# Power_Supply_adi.net
KiCad netlist of a schematic drawn in EAGLE
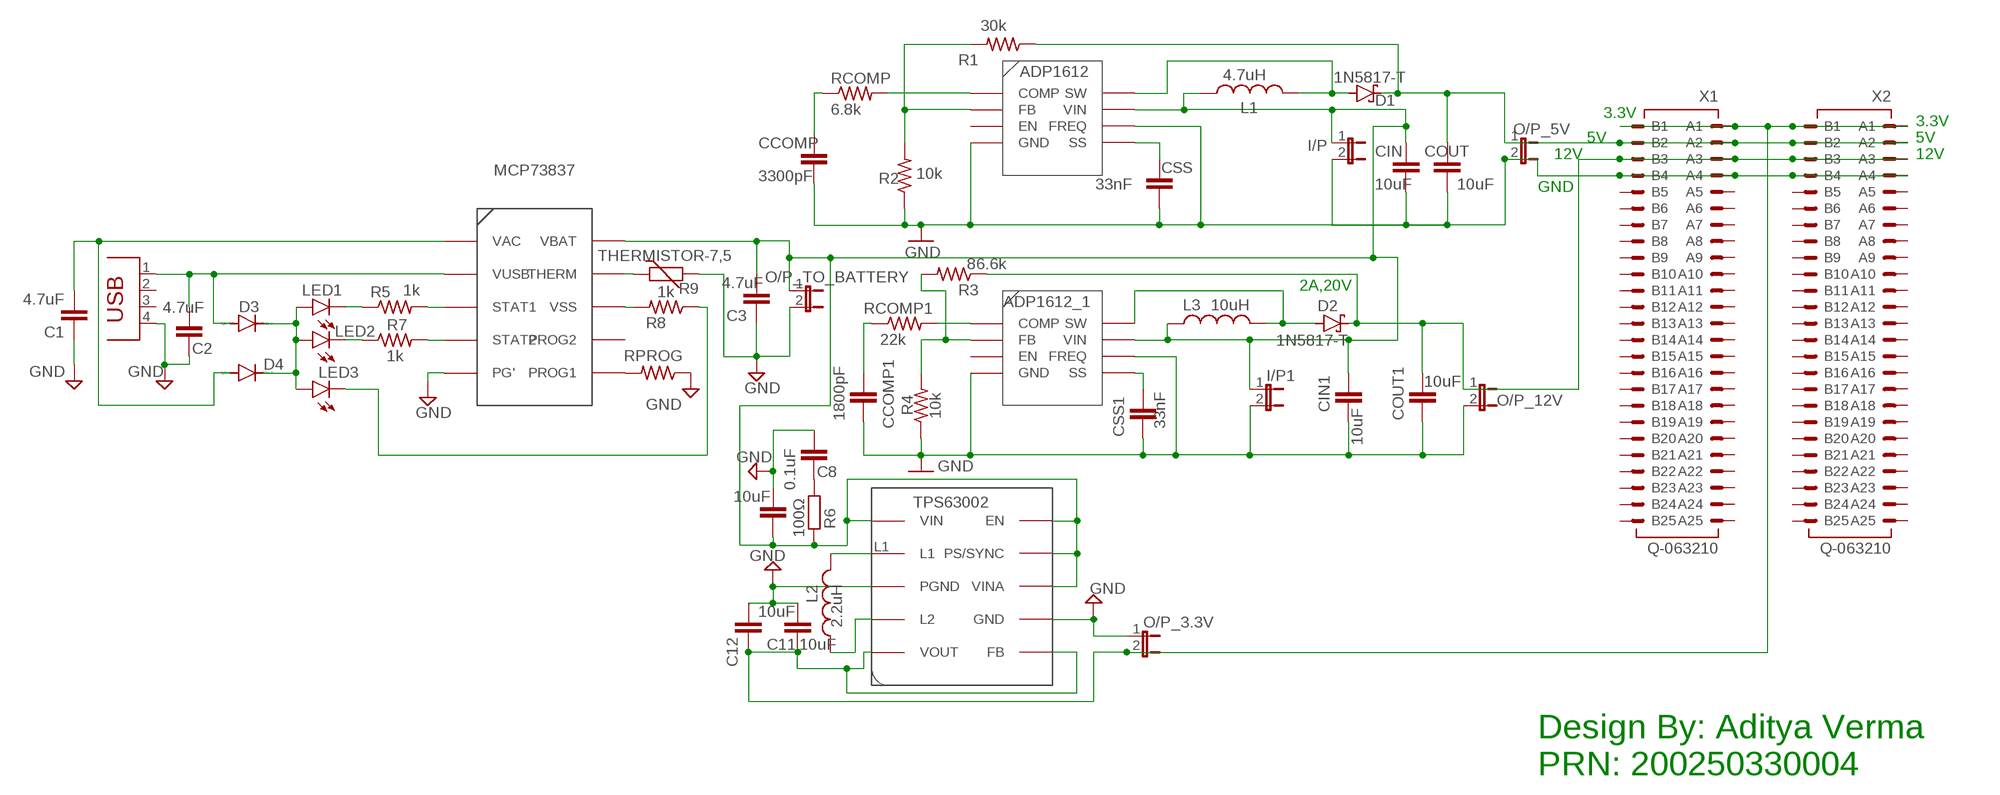
[diagram p0: schematic, sheet 1]

(export (version "E")
  (design (tool "Eeschema 10.0.6"))
  (components
    (comp (ref "ADP1612")
      (value "ADP1612_DEV")
      (footprint "eagle-import:ADP1612_FOOT")
      (libsource (lib "eagle-import") (part "ADP1612_DEV"))
    )
    (comp (ref "ADP1612_1")
      (value "ADP1612_DEV")
      (footprint "eagle-import:ADP1612_FOOT")
      (libsource (lib "eagle-import") (part "ADP1612_DEV"))
    )
    (comp (ref "C1")
      (value "4.7uF")
      (footprint "eagle-import:C2.5-3")
      (libsource (lib "eagle-import") (part "C2,5-3"))
    )
    (comp (ref "C2")
      (value "4.7uF")
      (footprint "eagle-import:C2.5-3")
      (libsource (lib "eagle-import") (part "C2,5-3"))
    )
    (comp (ref "C3")
      (value "4.7uF")
      (footprint "eagle-import:C2.5-3")
      (libsource (lib "eagle-import") (part "C2,5-3"))
    )
    (comp (ref "C8")
      (value "0.1uF")
      (footprint "eagle-import:C2.5-2")
      (libsource (lib "eagle-import") (part "C2.5/2"))
    )
    (comp (ref "C10")
      (value "10uF")
      (footprint "eagle-import:C2.5-2")
      (libsource (lib "eagle-import") (part "C2.5/2"))
    )
    (comp (ref "C11")
      (value "10uF")
      (footprint "eagle-import:C2.5-2")
      (libsource (lib "eagle-import") (part "C2.5/2"))
    )
    (comp (ref "C12")
      (value "10uF")
      (footprint "eagle-import:C2.5-2")
      (libsource (lib "eagle-import") (part "C2.5/2"))
    )
    (comp (ref "CCOMP")
      (value "3300pF")
      (footprint "eagle-import:C2.5-3")
      (libsource (lib "eagle-import") (part "C2,5-3"))
    )
    (comp (ref "CCOMP1")
      (value "1800pF")
      (footprint "eagle-import:C2.5-3")
      (libsource (lib "eagle-import") (part "C2,5-3"))
    )
    (comp (ref "CIN")
      (value "10uF")
      (footprint "eagle-import:C2.5-3")
      (libsource (lib "eagle-import") (part "C2,5-3"))
    )
    (comp (ref "CIN1")
      (value "10uF")
      (footprint "eagle-import:C2.5-3")
      (libsource (lib "eagle-import") (part "C2,5-3"))
    )
    (comp (ref "COUT")
      (value "10uF")
      (footprint "eagle-import:C2.5-3")
      (libsource (lib "eagle-import") (part "C2,5-3"))
    )
    (comp (ref "COUT1")
      (value "10uF")
      (footprint "eagle-import:C2.5-3")
      (libsource (lib "eagle-import") (part "C2,5-3"))
    )
    (comp (ref "CSS")
      (value "33nF")
      (footprint "eagle-import:C2.5-3")
      (libsource (lib "eagle-import") (part "C2,5-3"))
    )
    (comp (ref "CSS1")
      (value "33nF")
      (footprint "eagle-import:C2.5-3")
      (libsource (lib "eagle-import") (part "C2,5-3"))
    )
    (comp (ref "D1")
      (value "1N5817-T")
      (footprint "eagle-import:DO41-7.6")
      (libsource (lib "eagle-import") (part "1N5817-T"))
    )
    (comp (ref "D2")
      (value "1N5817-T")
      (footprint "eagle-import:DO41-7.6")
      (libsource (lib "eagle-import") (part "1N5817-T"))
    )
    (comp (ref "D3")
      (value "1N4004")
      (footprint "eagle-import:DO41-10")
      (libsource (lib "eagle-import") (part "1N4004"))
    )
    (comp (ref "D4")
      (value "1N4004")
      (footprint "eagle-import:DO41-10")
      (libsource (lib "eagle-import") (part "1N4004"))
    )
    (comp (ref "I/P")
      (value "JP1E")
      (footprint "eagle-import:JP1")
      (libsource (lib "eagle-import") (part "JP1E"))
    )
    (comp (ref "I/P1")
      (value "JP1E")
      (footprint "eagle-import:JP1")
      (libsource (lib "eagle-import") (part "JP1E"))
    )
    (comp (ref "L1")
      (value "4.7uH")
      (footprint "eagle-import:0204_7")
      (libsource (lib "eagle-import") (part "L-US0204/7"))
    )
    (comp (ref "L2")
      (value "2.2uH")
      (footprint "eagle-import:0207_7")
      (libsource (lib "eagle-import") (part "L-US0207/7"))
    )
    (comp (ref "L3")
      (value "10uH")
      (footprint "eagle-import:0204_7")
      (libsource (lib "eagle-import") (part "L-US0204/7"))
    )
    (comp (ref "LED1")
      (value "LED3MM")
      (footprint "eagle-import:LED3MM")
      (libsource (lib "eagle-import") (part "LED3MM"))
    )
    (comp (ref "LED2")
      (value "LEDLD260")
      (footprint "eagle-import:LD260")
      (libsource (lib "eagle-import") (part "LEDLD260"))
    )
    (comp (ref "LED3")
      (value "LED3MM")
      (footprint "eagle-import:LED3MM")
      (libsource (lib "eagle-import") (part "LED3MM"))
    )
    (comp (ref "MCP73837")
      (value "MCP73837-DEV")
      (footprint "eagle-import:MCP73837")
      (libsource (lib "eagle-import") (part "MCP73837-DEV"))
    )
    (comp (ref "O/P_3.3V")
      (value "JP1E")
      (footprint "eagle-import:JP1")
      (libsource (lib "eagle-import") (part "JP1E"))
    )
    (comp (ref "O/P_5V")
      (value "JP1E")
      (footprint "eagle-import:JP1")
      (libsource (lib "eagle-import") (part "JP1E"))
    )
    (comp (ref "O/P_12V")
      (value "JP1E")
      (footprint "eagle-import:JP1")
      (libsource (lib "eagle-import") (part "JP1E"))
    )
    (comp (ref "O/P_TO_BATTERY")
      (value "JP1E")
      (footprint "eagle-import:JP1")
      (libsource (lib "eagle-import") (part "JP1E"))
    )
    (comp (ref "R1")
      (value "30k")
      (footprint "eagle-import:0204V")
      (libsource (lib "eagle-import") (part "R-US_0204/2V"))
    )
    (comp (ref "R2")
      (value "10k")
      (footprint "eagle-import:0204V")
      (libsource (lib "eagle-import") (part "R-US_0204/2V"))
    )
    (comp (ref "R3")
      (value "86.6k")
      (footprint "eagle-import:0204V")
      (libsource (lib "eagle-import") (part "R-US_0204/2V"))
    )
    (comp (ref "R4")
      (value "10k")
      (footprint "eagle-import:0204V")
      (libsource (lib "eagle-import") (part "R-US_0204/2V"))
    )
    (comp (ref "R5")
      (value "1k")
      (footprint "eagle-import:0204V")
      (libsource (lib "eagle-import") (part "R-US_0204/2V"))
    )
    (comp (ref "R6")
      (value "100Ω")
      (footprint "eagle-import:0207_10")
      (libsource (lib "eagle-import") (part "R-EU_0207/10"))
    )
    (comp (ref "R7")
      (value "1k")
      (footprint "eagle-import:0204V")
      (libsource (lib "eagle-import") (part "R-US_0204/2V"))
    )
    (comp (ref "R8")
      (value "1k")
      (footprint "eagle-import:0204V")
      (libsource (lib "eagle-import") (part "R-US_0204/2V"))
    )
    (comp (ref "R9")
      (value "THERMISTOR-7,5")
      (footprint "eagle-import:R-7,5")
      (libsource (lib "eagle-import") (part "THERMISTOR-7,5"))
    )
    (comp (ref "RCOMP")
      (value "6.8k")
      (footprint "eagle-import:0204V")
      (libsource (lib "eagle-import") (part "R-US_0204/2V"))
    )
    (comp (ref "RCOMP1")
      (value "22k")
      (footprint "eagle-import:0204V")
      (libsource (lib "eagle-import") (part "R-US_0204/2V"))
    )
    (comp (ref "RPROG")
      (value "R-US_0204/2V")
      (footprint "eagle-import:0204V")
      (libsource (lib "eagle-import") (part "R-US_0204/2V"))
    )
    (comp (ref "TPS63002")
      (value "TPS63002")
      (footprint "eagle-import:TPS63002")
      (libsource (lib "eagle-import") (part "TPS63002"))
    )
    (comp (ref "USB")
      (value "PN61729")
      (footprint "eagle-import:PN61729")
      (libsource (lib "eagle-import") (part "PN61729"))
    )
    (comp (ref "X1")
      (value "Q-063210")
      (footprint "eagle-import:063210")
      (libsource (lib "eagle-import") (part "Q-063210"))
    )
    (comp (ref "X2")
      (value "Q-063210")
      (footprint "eagle-import:063210")
      (libsource (lib "eagle-import") (part "Q-063210"))
    )
  )
  (nets
    (net (code "1") (name "GND") (class "Default")
      (node (ref "ADP1612") (pin "FREQ") (pinfunction "FREQ_FREQ") (pintype "bidirectional"))
      (node (ref "ADP1612") (pin "GND") (pinfunction "GND_GND") (pintype "bidirectional"))
      (node (ref "ADP1612_1") (pin "FREQ") (pinfunction "FREQ_FREQ") (pintype "bidirectional"))
      (node (ref "ADP1612_1") (pin "GND") (pinfunction "GND_GND") (pintype "bidirectional"))
      (node (ref "C1") (pin "1") (pinfunction "1_1") (pintype "passive"))
      (node (ref "C10") (pin "2") (pinfunction "2_2") (pintype "passive"))
      (node (ref "C11") (pin "2") (pinfunction "2_2") (pintype "passive"))
      (node (ref "C12") (pin "2") (pinfunction "2_2") (pintype "passive"))
      (node (ref "C2") (pin "1") (pinfunction "1_1") (pintype "passive"))
      (node (ref "C3") (pin "1") (pinfunction "1_1") (pintype "passive"))
      (node (ref "C8") (pin "2") (pinfunction "2_2") (pintype "passive"))
      (node (ref "CCOMP") (pin "2") (pinfunction "2_2") (pintype "passive"))
      (node (ref "CCOMP1") (pin "2") (pinfunction "2_2") (pintype "passive"))
      (node (ref "CIN") (pin "2") (pinfunction "2_2") (pintype "passive"))
      (node (ref "CIN1") (pin "2") (pinfunction "2_2") (pintype "passive"))
      (node (ref "COUT") (pin "2") (pinfunction "2_2") (pintype "passive"))
      (node (ref "COUT1") (pin "2") (pinfunction "2_2") (pintype "passive"))
      (node (ref "CSS") (pin "2") (pinfunction "2_2") (pintype "passive"))
      (node (ref "CSS1") (pin "2") (pinfunction "2_2") (pintype "passive"))
      (node (ref "I/P") (pin "2") (pinfunction "2_2") (pintype "passive"))
      (node (ref "I/P1") (pin "2") (pinfunction "2_2") (pintype "passive"))
      (node (ref "MCP73837") (pin "PG'") (pinfunction "PG'_PG'") (pintype "bidirectional"))
      (node (ref "O/P_12V") (pin "2") (pinfunction "2_2") (pintype "passive"))
      (node (ref "O/P_3.3V") (pin "1") (pinfunction "1_1") (pintype "passive"))
      (node (ref "O/P_5V") (pin "2") (pinfunction "2_2") (pintype "passive"))
      (node (ref "O/P_TO_BATTERY") (pin "2") (pinfunction "2_2") (pintype "passive"))
      (node (ref "R2") (pin "1") (pinfunction "1_1") (pintype "passive"))
      (node (ref "R4") (pin "1") (pinfunction "1_1") (pintype "passive"))
      (node (ref "R9") (pin "2") (pinfunction "2_2") (pintype "passive"))
      (node (ref "RPROG") (pin "1") (pinfunction "1_1") (pintype "passive"))
      (node (ref "TPS63002") (pin "GND") (pinfunction "GND_GND") (pintype "bidirectional"))
      (node (ref "TPS63002") (pin "PGND") (pinfunction "PGND_PGND") (pintype "bidirectional"))
      (node (ref "USB") (pin "4") (pinfunction "4_4") (pintype "passive"))
      (node (ref "X1") (pin "A4") (pinfunction "A4_A4") (pintype "passive"))
      (node (ref "X1") (pin "B4") (pinfunction "B4_B4") (pintype "passive"))
      (node (ref "X2") (pin "A4") (pinfunction "A4_A4") (pintype "passive"))
      (node (ref "X2") (pin "B4") (pinfunction "B4_B4") (pintype "passive"))
    )
    (net (code "2") (name "Net-(ADP1612-PadCOMP)") (class "Default")
      (node (ref "ADP1612") (pin "COMP") (pinfunction "COMP_COMP") (pintype "bidirectional"))
      (node (ref "RCOMP") (pin "2") (pinfunction "2_2") (pintype "passive"))
    )
    (net (code "3") (name "Net-(ADP1612-PadFB)") (class "Default")
      (node (ref "ADP1612") (pin "FB") (pinfunction "FB_FB") (pintype "bidirectional"))
      (node (ref "R1") (pin "2") (pinfunction "2_2") (pintype "passive"))
      (node (ref "R2") (pin "2") (pinfunction "2_2") (pintype "passive"))
    )
    (net (code "4") (name "Net-(ADP1612-PadSS)") (class "Default")
      (node (ref "ADP1612") (pin "SS") (pinfunction "SS_SS") (pintype "bidirectional"))
      (node (ref "CSS") (pin "1") (pinfunction "1_1") (pintype "passive"))
    )
    (net (code "5") (name "Net-(ADP1612-PadSW)") (class "Default")
      (node (ref "ADP1612") (pin "SW") (pinfunction "SW_SW") (pintype "bidirectional"))
      (node (ref "D1") (pin "A") (pinfunction "A_A") (pintype "passive"))
      (node (ref "L1") (pin "2") (pinfunction "2_2") (pintype "passive"))
    )
    (net (code "6") (name "Net-(ADP1612-PadVIN)") (class "Default")
      (node (ref "ADP1612") (pin "VIN") (pinfunction "VIN_VIN") (pintype "bidirectional"))
      (node (ref "ADP1612_1") (pin "VIN") (pinfunction "VIN_VIN") (pintype "bidirectional"))
      (node (ref "C10") (pin "1") (pinfunction "1_1") (pintype "passive"))
      (node (ref "C3") (pin "2") (pinfunction "2_2") (pintype "passive"))
      (node (ref "CIN") (pin "1") (pinfunction "1_1") (pintype "passive"))
      (node (ref "CIN1") (pin "1") (pinfunction "1_1") (pintype "passive"))
      (node (ref "I/P") (pin "1") (pinfunction "1_1") (pintype "passive"))
      (node (ref "I/P1") (pin "1") (pinfunction "1_1") (pintype "passive"))
      (node (ref "L1") (pin "1") (pinfunction "1_1") (pintype "passive"))
      (node (ref "L3") (pin "1") (pinfunction "1_1") (pintype "passive"))
      (node (ref "MCP73837") (pin "VBAT") (pinfunction "VBAT_VBAT") (pintype "bidirectional"))
      (node (ref "O/P_TO_BATTERY") (pin "1") (pinfunction "1_1") (pintype "passive"))
      (node (ref "R6") (pin "1") (pinfunction "1_1") (pintype "passive"))
      (node (ref "TPS63002") (pin "EN") (pinfunction "EN_EN") (pintype "bidirectional"))
      (node (ref "TPS63002") (pin "PS/SYNC") (pinfunction "PS/SYNC_PS/SYNC") (pintype "bidirectional"))
      (node (ref "TPS63002") (pin "VIN") (pinfunction "VIN_VIN") (pintype "bidirectional"))
      (node (ref "TPS63002") (pin "VINA") (pinfunction "VINA_VINA") (pintype "bidirectional"))
    )
    (net (code "7") (name "Net-(ADP1612_1-PadCOMP)") (class "Default")
      (node (ref "ADP1612_1") (pin "COMP") (pinfunction "COMP_COMP") (pintype "bidirectional"))
      (node (ref "RCOMP1") (pin "2") (pinfunction "2_2") (pintype "passive"))
    )
    (net (code "8") (name "Net-(ADP1612_1-PadFB)") (class "Default")
      (node (ref "ADP1612_1") (pin "FB") (pinfunction "FB_FB") (pintype "bidirectional"))
      (node (ref "R3") (pin "2") (pinfunction "2_2") (pintype "passive"))
      (node (ref "R4") (pin "2") (pinfunction "2_2") (pintype "passive"))
    )
    (net (code "9") (name "Net-(ADP1612_1-PadSS)") (class "Default")
      (node (ref "ADP1612_1") (pin "SS") (pinfunction "SS_SS") (pintype "bidirectional"))
      (node (ref "CSS1") (pin "1") (pinfunction "1_1") (pintype "passive"))
    )
    (net (code "10") (name "Net-(ADP1612_1-PadSW)") (class "Default")
      (node (ref "ADP1612_1") (pin "SW") (pinfunction "SW_SW") (pintype "bidirectional"))
      (node (ref "D2") (pin "A") (pinfunction "A_A") (pintype "passive"))
      (node (ref "L3") (pin "2") (pinfunction "2_2") (pintype "passive"))
    )
    (net (code "11") (name "Net-(C1-Pad2)") (class "Default")
      (node (ref "C1") (pin "2") (pinfunction "2_2") (pintype "passive"))
      (node (ref "D4") (pin "A") (pinfunction "A_A") (pintype "passive"))
      (node (ref "MCP73837") (pin "VAC") (pinfunction "VAC_VAC") (pintype "bidirectional"))
    )
    (net (code "12") (name "Net-(C2-Pad2)") (class "Default")
      (node (ref "C2") (pin "2") (pinfunction "2_2") (pintype "passive"))
      (node (ref "D3") (pin "A") (pinfunction "A_A") (pintype "passive"))
      (node (ref "MCP73837") (pin "VUSB") (pinfunction "VUSB_VUSB") (pintype "bidirectional"))
      (node (ref "USB") (pin "1") (pinfunction "1_1") (pintype "passive"))
    )
    (net (code "13") (name "Net-(C8-Pad1)") (class "Default")
      (node (ref "C8") (pin "1") (pinfunction "1_1") (pintype "passive"))
      (node (ref "R6") (pin "2") (pinfunction "2_2") (pintype "passive"))
    )
    (net (code "14") (name "Net-(C11-Pad1)") (class "Default")
      (node (ref "C11") (pin "1") (pinfunction "1_1") (pintype "passive"))
      (node (ref "C12") (pin "1") (pinfunction "1_1") (pintype "passive"))
      (node (ref "O/P_3.3V") (pin "2") (pinfunction "2_2") (pintype "passive"))
      (node (ref "TPS63002") (pin "FB") (pinfunction "FB_FB") (pintype "bidirectional"))
      (node (ref "TPS63002") (pin "VOUT") (pinfunction "VOUT_VOUT") (pintype "bidirectional"))
      (node (ref "X1") (pin "A1") (pinfunction "A1_A1") (pintype "passive"))
      (node (ref "X1") (pin "B1") (pinfunction "B1_B1") (pintype "passive"))
      (node (ref "X2") (pin "A1") (pinfunction "A1_A1") (pintype "passive"))
      (node (ref "X2") (pin "B1") (pinfunction "B1_B1") (pintype "passive"))
    )
    (net (code "15") (name "Net-(CCOMP-Pad1)") (class "Default")
      (node (ref "CCOMP") (pin "1") (pinfunction "1_1") (pintype "passive"))
      (node (ref "RCOMP") (pin "1") (pinfunction "1_1") (pintype "passive"))
    )
    (net (code "16") (name "Net-(CCOMP1-Pad1)") (class "Default")
      (node (ref "CCOMP1") (pin "1") (pinfunction "1_1") (pintype "passive"))
      (node (ref "RCOMP1") (pin "1") (pinfunction "1_1") (pintype "passive"))
    )
    (net (code "17") (name "Net-(COUT-Pad1)") (class "Default")
      (node (ref "COUT") (pin "1") (pinfunction "1_1") (pintype "passive"))
      (node (ref "D1") (pin "C") (pinfunction "C_C") (pintype "passive"))
      (node (ref "O/P_5V") (pin "1") (pinfunction "1_1") (pintype "passive"))
      (node (ref "R1") (pin "1") (pinfunction "1_1") (pintype "passive"))
      (node (ref "X1") (pin "A2") (pinfunction "A2_A2") (pintype "passive"))
      (node (ref "X1") (pin "B2") (pinfunction "B2_B2") (pintype "passive"))
      (node (ref "X2") (pin "A2") (pinfunction "A2_A2") (pintype "passive"))
      (node (ref "X2") (pin "B2") (pinfunction "B2_B2") (pintype "passive"))
    )
    (net (code "18") (name "Net-(COUT1-Pad1)") (class "Default")
      (node (ref "COUT1") (pin "1") (pinfunction "1_1") (pintype "passive"))
      (node (ref "D2") (pin "C") (pinfunction "C_C") (pintype "passive"))
      (node (ref "O/P_12V") (pin "1") (pinfunction "1_1") (pintype "passive"))
      (node (ref "R3") (pin "1") (pinfunction "1_1") (pintype "passive"))
      (node (ref "X1") (pin "A3") (pinfunction "A3_A3") (pintype "passive"))
      (node (ref "X1") (pin "B3") (pinfunction "B3_B3") (pintype "passive"))
      (node (ref "X2") (pin "A3") (pinfunction "A3_A3") (pintype "passive"))
      (node (ref "X2") (pin "B3") (pinfunction "B3_B3") (pintype "passive"))
    )
    (net (code "19") (name "Net-(D3-PadC)") (class "Default")
      (node (ref "D3") (pin "C") (pinfunction "C_C") (pintype "passive"))
      (node (ref "D4") (pin "C") (pinfunction "C_C") (pintype "passive"))
      (node (ref "LED1") (pin "A") (pinfunction "A_A") (pintype "passive"))
      (node (ref "LED2") (pin "A") (pinfunction "A_A") (pintype "passive"))
      (node (ref "LED3") (pin "A") (pinfunction "A_A") (pintype "passive"))
    )
    (net (code "20") (name "Net-(L2-Pad1)") (class "Default")
      (node (ref "L2") (pin "1") (pinfunction "1_1") (pintype "passive"))
      (node (ref "TPS63002") (pin "L1") (pinfunction "L1_L1") (pintype "bidirectional"))
    )
    (net (code "21") (name "Net-(L2-Pad2)") (class "Default")
      (node (ref "L2") (pin "2") (pinfunction "2_2") (pintype "passive"))
      (node (ref "TPS63002") (pin "L2") (pinfunction "L2_L2") (pintype "bidirectional"))
    )
    (net (code "22") (name "Net-(LED1-C)") (class "Default")
      (node (ref "LED1") (pin "K") (pinfunction "C_K") (pintype "passive"))
      (node (ref "R5") (pin "1") (pinfunction "1_1") (pintype "passive"))
    )
    (net (code "23") (name "Net-(LED2-C)") (class "Default")
      (node (ref "LED2") (pin "K") (pinfunction "C_K") (pintype "passive"))
      (node (ref "R7") (pin "1") (pinfunction "1_1") (pintype "passive"))
    )
    (net (code "24") (name "Net-(LED3-C)") (class "Default")
      (node (ref "LED3") (pin "K") (pinfunction "C_K") (pintype "passive"))
      (node (ref "R8") (pin "1") (pinfunction "1_1") (pintype "passive"))
    )
    (net (code "25") (name "Net-(MCP73837-PadPROG1)") (class "Default")
      (node (ref "MCP73837") (pin "PROG1") (pinfunction "PROG1_PROG1") (pintype "bidirectional"))
      (node (ref "RPROG") (pin "2") (pinfunction "2_2") (pintype "passive"))
    )
    (net (code "26") (name "Net-(MCP73837-PadSTAT1)") (class "Default")
      (node (ref "MCP73837") (pin "STAT1") (pinfunction "STAT1_STAT1") (pintype "bidirectional"))
      (node (ref "R5") (pin "2") (pinfunction "2_2") (pintype "passive"))
    )
    (net (code "27") (name "Net-(MCP73837-PadSTAT2)") (class "Default")
      (node (ref "MCP73837") (pin "STAT2") (pinfunction "STAT2_STAT2") (pintype "bidirectional"))
      (node (ref "R7") (pin "2") (pinfunction "2_2") (pintype "passive"))
    )
    (net (code "28") (name "Net-(MCP73837-PadTHERM)") (class "Default")
      (node (ref "MCP73837") (pin "THERM") (pinfunction "THERM_THERM") (pintype "bidirectional"))
      (node (ref "R9") (pin "1") (pinfunction "1_1") (pintype "passive"))
    )
    (net (code "29") (name "Net-(MCP73837-PadVSS)") (class "Default")
      (node (ref "MCP73837") (pin "VSS") (pinfunction "VSS_VSS") (pintype "bidirectional"))
      (node (ref "R8") (pin "2") (pinfunction "2_2") (pintype "passive"))
    )
    (net (code "30") (name "unconnected-(ADP1612-PadEN)") (class "Default")
      (node (ref "ADP1612") (pin "EN") (pinfunction "EN_EN") (pintype "bidirectional"))
    )
    (net (code "31") (name "unconnected-(ADP1612_1-PadEN)") (class "Default")
      (node (ref "ADP1612_1") (pin "EN") (pinfunction "EN_EN") (pintype "bidirectional"))
    )
    (net (code "32") (name "unconnected-(MCP73837-PadPROG2)") (class "Default")
      (node (ref "MCP73837") (pin "PROG2") (pinfunction "PROG2_PROG2") (pintype "bidirectional"))
    )
    (net (code "33") (name "unconnected-(USB-Pad2)") (class "Default")
      (node (ref "USB") (pin "2") (pinfunction "2_2") (pintype "passive"))
    )
    (net (code "34") (name "unconnected-(USB-Pad3)") (class "Default")
      (node (ref "USB") (pin "3") (pinfunction "3_3") (pintype "passive"))
    )
    (net (code "35") (name "unconnected-(X1-PadA5)") (class "Default")
      (node (ref "X1") (pin "A5") (pinfunction "A5_A5") (pintype "passive"))
    )
    (net (code "36") (name "unconnected-(X1-PadA6)") (class "Default")
      (node (ref "X1") (pin "A6") (pinfunction "A6_A6") (pintype "passive"))
    )
    (net (code "37") (name "unconnected-(X1-PadA7)") (class "Default")
      (node (ref "X1") (pin "A7") (pinfunction "A7_A7") (pintype "passive"))
    )
    (net (code "38") (name "unconnected-(X1-PadA8)") (class "Default")
      (node (ref "X1") (pin "A8") (pinfunction "A8_A8") (pintype "passive"))
    )
    (net (code "39") (name "unconnected-(X1-PadA9)") (class "Default")
      (node (ref "X1") (pin "A9") (pinfunction "A9_A9") (pintype "passive"))
    )
    (net (code "40") (name "unconnected-(X1-PadA10)") (class "Default")
      (node (ref "X1") (pin "A10") (pinfunction "A10_A10") (pintype "passive"))
    )
    (net (code "41") (name "unconnected-(X1-PadA11)") (class "Default")
      (node (ref "X1") (pin "A11") (pinfunction "A11_A11") (pintype "passive"))
    )
    (net (code "42") (name "unconnected-(X1-PadA12)") (class "Default")
      (node (ref "X1") (pin "A12") (pinfunction "A12_A12") (pintype "passive"))
    )
    (net (code "43") (name "unconnected-(X1-PadA13)") (class "Default")
      (node (ref "X1") (pin "A13") (pinfunction "A13_A13") (pintype "passive"))
    )
    (net (code "44") (name "unconnected-(X1-PadA14)") (class "Default")
      (node (ref "X1") (pin "A14") (pinfunction "A14_A14") (pintype "passive"))
    )
    (net (code "45") (name "unconnected-(X1-PadA15)") (class "Default")
      (node (ref "X1") (pin "A15") (pinfunction "A15_A15") (pintype "passive"))
    )
    (net (code "46") (name "unconnected-(X1-PadA16)") (class "Default")
      (node (ref "X1") (pin "A16") (pinfunction "A16_A16") (pintype "passive"))
    )
    (net (code "47") (name "unconnected-(X1-PadA17)") (class "Default")
      (node (ref "X1") (pin "A17") (pinfunction "A17_A17") (pintype "passive"))
    )
    (net (code "48") (name "unconnected-(X1-PadA18)") (class "Default")
      (node (ref "X1") (pin "A18") (pinfunction "A18_A18") (pintype "passive"))
    )
    (net (code "49") (name "unconnected-(X1-PadA19)") (class "Default")
      (node (ref "X1") (pin "A19") (pinfunction "A19_A19") (pintype "passive"))
    )
    (net (code "50") (name "unconnected-(X1-PadA20)") (class "Default")
      (node (ref "X1") (pin "A20") (pinfunction "A20_A20") (pintype "passive"))
    )
    (net (code "51") (name "unconnected-(X1-PadA21)") (class "Default")
      (node (ref "X1") (pin "A21") (pinfunction "A21_A21") (pintype "passive"))
    )
    (net (code "52") (name "unconnected-(X1-PadA22)") (class "Default")
      (node (ref "X1") (pin "A22") (pinfunction "A22_A22") (pintype "passive"))
    )
    (net (code "53") (name "unconnected-(X1-PadA23)") (class "Default")
      (node (ref "X1") (pin "A23") (pinfunction "A23_A23") (pintype "passive"))
    )
    (net (code "54") (name "unconnected-(X1-PadA24)") (class "Default")
      (node (ref "X1") (pin "A24") (pinfunction "A24_A24") (pintype "passive"))
    )
    (net (code "55") (name "unconnected-(X1-PadA25)") (class "Default")
      (node (ref "X1") (pin "A25") (pinfunction "A25_A25") (pintype "passive"))
    )
    (net (code "56") (name "unconnected-(X1-PadB5)") (class "Default")
      (node (ref "X1") (pin "B5") (pinfunction "B5_B5") (pintype "passive"))
    )
    (net (code "57") (name "unconnected-(X1-PadB6)") (class "Default")
      (node (ref "X1") (pin "B6") (pinfunction "B6_B6") (pintype "passive"))
    )
    (net (code "58") (name "unconnected-(X1-PadB7)") (class "Default")
      (node (ref "X1") (pin "B7") (pinfunction "B7_B7") (pintype "passive"))
    )
    (net (code "59") (name "unconnected-(X1-PadB8)") (class "Default")
      (node (ref "X1") (pin "B8") (pinfunction "B8_B8") (pintype "passive"))
    )
    (net (code "60") (name "unconnected-(X1-PadB9)") (class "Default")
      (node (ref "X1") (pin "B9") (pinfunction "B9_B9") (pintype "passive"))
    )
    (net (code "61") (name "unconnected-(X1-PadB10)") (class "Default")
      (node (ref "X1") (pin "B10") (pinfunction "B10_B10") (pintype "passive"))
    )
    (net (code "62") (name "unconnected-(X1-PadB11)") (class "Default")
      (node (ref "X1") (pin "B11") (pinfunction "B11_B11") (pintype "passive"))
    )
    (net (code "63") (name "unconnected-(X1-PadB12)") (class "Default")
      (node (ref "X1") (pin "B12") (pinfunction "B12_B12") (pintype "passive"))
    )
    (net (code "64") (name "unconnected-(X1-PadB13)") (class "Default")
      (node (ref "X1") (pin "B13") (pinfunction "B13_B13") (pintype "passive"))
    )
    (net (code "65") (name "unconnected-(X1-PadB14)") (class "Default")
      (node (ref "X1") (pin "B14") (pinfunction "B14_B14") (pintype "passive"))
    )
    (net (code "66") (name "unconnected-(X1-PadB15)") (class "Default")
      (node (ref "X1") (pin "B15") (pinfunction "B15_B15") (pintype "passive"))
    )
    (net (code "67") (name "unconnected-(X1-PadB16)") (class "Default")
      (node (ref "X1") (pin "B16") (pinfunction "B16_B16") (pintype "passive"))
    )
    (net (code "68") (name "unconnected-(X1-PadB17)") (class "Default")
      (node (ref "X1") (pin "B17") (pinfunction "B17_B17") (pintype "passive"))
    )
    (net (code "69") (name "unconnected-(X1-PadB18)") (class "Default")
      (node (ref "X1") (pin "B18") (pinfunction "B18_B18") (pintype "passive"))
    )
    (net (code "70") (name "unconnected-(X1-PadB19)") (class "Default")
      (node (ref "X1") (pin "B19") (pinfunction "B19_B19") (pintype "passive"))
    )
    (net (code "71") (name "unconnected-(X1-PadB20)") (class "Default")
      (node (ref "X1") (pin "B20") (pinfunction "B20_B20") (pintype "passive"))
    )
    (net (code "72") (name "unconnected-(X1-PadB21)") (class "Default")
      (node (ref "X1") (pin "B21") (pinfunction "B21_B21") (pintype "passive"))
    )
    (net (code "73") (name "unconnected-(X1-PadB22)") (class "Default")
      (node (ref "X1") (pin "B22") (pinfunction "B22_B22") (pintype "passive"))
    )
    (net (code "74") (name "unconnected-(X1-PadB23)") (class "Default")
      (node (ref "X1") (pin "B23") (pinfunction "B23_B23") (pintype "passive"))
    )
    (net (code "75") (name "unconnected-(X1-PadB24)") (class "Default")
      (node (ref "X1") (pin "B24") (pinfunction "B24_B24") (pintype "passive"))
    )
    (net (code "76") (name "unconnected-(X1-PadB25)") (class "Default")
      (node (ref "X1") (pin "B25") (pinfunction "B25_B25") (pintype "passive"))
    )
    (net (code "77") (name "unconnected-(X2-PadA5)") (class "Default")
      (node (ref "X2") (pin "A5") (pinfunction "A5_A5") (pintype "passive"))
    )
    (net (code "78") (name "unconnected-(X2-PadA6)") (class "Default")
      (node (ref "X2") (pin "A6") (pinfunction "A6_A6") (pintype "passive"))
    )
    (net (code "79") (name "unconnected-(X2-PadA7)") (class "Default")
      (node (ref "X2") (pin "A7") (pinfunction "A7_A7") (pintype "passive"))
    )
    (net (code "80") (name "unconnected-(X2-PadA8)") (class "Default")
      (node (ref "X2") (pin "A8") (pinfunction "A8_A8") (pintype "passive"))
    )
    (net (code "81") (name "unconnected-(X2-PadA9)") (class "Default")
      (node (ref "X2") (pin "A9") (pinfunction "A9_A9") (pintype "passive"))
    )
    (net (code "82") (name "unconnected-(X2-PadA10)") (class "Default")
      (node (ref "X2") (pin "A10") (pinfunction "A10_A10") (pintype "passive"))
    )
    (net (code "83") (name "unconnected-(X2-PadA11)") (class "Default")
      (node (ref "X2") (pin "A11") (pinfunction "A11_A11") (pintype "passive"))
    )
    (net (code "84") (name "unconnected-(X2-PadA12)") (class "Default")
      (node (ref "X2") (pin "A12") (pinfunction "A12_A12") (pintype "passive"))
    )
    (net (code "85") (name "unconnected-(X2-PadA13)") (class "Default")
      (node (ref "X2") (pin "A13") (pinfunction "A13_A13") (pintype "passive"))
    )
    (net (code "86") (name "unconnected-(X2-PadA14)") (class "Default")
      (node (ref "X2") (pin "A14") (pinfunction "A14_A14") (pintype "passive"))
    )
    (net (code "87") (name "unconnected-(X2-PadA15)") (class "Default")
      (node (ref "X2") (pin "A15") (pinfunction "A15_A15") (pintype "passive"))
    )
    (net (code "88") (name "unconnected-(X2-PadA16)") (class "Default")
      (node (ref "X2") (pin "A16") (pinfunction "A16_A16") (pintype "passive"))
    )
    (net (code "89") (name "unconnected-(X2-PadA17)") (class "Default")
      (node (ref "X2") (pin "A17") (pinfunction "A17_A17") (pintype "passive"))
    )
    (net (code "90") (name "unconnected-(X2-PadA18)") (class "Default")
      (node (ref "X2") (pin "A18") (pinfunction "A18_A18") (pintype "passive"))
    )
    (net (code "91") (name "unconnected-(X2-PadA19)") (class "Default")
      (node (ref "X2") (pin "A19") (pinfunction "A19_A19") (pintype "passive"))
    )
    (net (code "92") (name "unconnected-(X2-PadA20)") (class "Default")
      (node (ref "X2") (pin "A20") (pinfunction "A20_A20") (pintype "passive"))
    )
    (net (code "93") (name "unconnected-(X2-PadA21)") (class "Default")
      (node (ref "X2") (pin "A21") (pinfunction "A21_A21") (pintype "passive"))
    )
    (net (code "94") (name "unconnected-(X2-PadA22)") (class "Default")
      (node (ref "X2") (pin "A22") (pinfunction "A22_A22") (pintype "passive"))
    )
    (net (code "95") (name "unconnected-(X2-PadA23)") (class "Default")
      (node (ref "X2") (pin "A23") (pinfunction "A23_A23") (pintype "passive"))
    )
    (net (code "96") (name "unconnected-(X2-PadA24)") (class "Default")
      (node (ref "X2") (pin "A24") (pinfunction "A24_A24") (pintype "passive"))
    )
    (net (code "97") (name "unconnected-(X2-PadA25)") (class "Default")
      (node (ref "X2") (pin "A25") (pinfunction "A25_A25") (pintype "passive"))
    )
    (net (code "98") (name "unconnected-(X2-PadB5)") (class "Default")
      (node (ref "X2") (pin "B5") (pinfunction "B5_B5") (pintype "passive"))
    )
    (net (code "99") (name "unconnected-(X2-PadB6)") (class "Default")
      (node (ref "X2") (pin "B6") (pinfunction "B6_B6") (pintype "passive"))
    )
    (net (code "100") (name "unconnected-(X2-PadB7)") (class "Default")
      (node (ref "X2") (pin "B7") (pinfunction "B7_B7") (pintype "passive"))
    )
    (net (code "101") (name "unconnected-(X2-PadB8)") (class "Default")
      (node (ref "X2") (pin "B8") (pinfunction "B8_B8") (pintype "passive"))
    )
    (net (code "102") (name "unconnected-(X2-PadB9)") (class "Default")
      (node (ref "X2") (pin "B9") (pinfunction "B9_B9") (pintype "passive"))
    )
    (net (code "103") (name "unconnected-(X2-PadB10)") (class "Default")
      (node (ref "X2") (pin "B10") (pinfunction "B10_B10") (pintype "passive"))
    )
    (net (code "104") (name "unconnected-(X2-PadB11)") (class "Default")
      (node (ref "X2") (pin "B11") (pinfunction "B11_B11") (pintype "passive"))
    )
    (net (code "105") (name "unconnected-(X2-PadB12)") (class "Default")
      (node (ref "X2") (pin "B12") (pinfunction "B12_B12") (pintype "passive"))
    )
    (net (code "106") (name "unconnected-(X2-PadB13)") (class "Default")
      (node (ref "X2") (pin "B13") (pinfunction "B13_B13") (pintype "passive"))
    )
    (net (code "107") (name "unconnected-(X2-PadB14)") (class "Default")
      (node (ref "X2") (pin "B14") (pinfunction "B14_B14") (pintype "passive"))
    )
    (net (code "108") (name "unconnected-(X2-PadB15)") (class "Default")
      (node (ref "X2") (pin "B15") (pinfunction "B15_B15") (pintype "passive"))
    )
    (net (code "109") (name "unconnected-(X2-PadB16)") (class "Default")
      (node (ref "X2") (pin "B16") (pinfunction "B16_B16") (pintype "passive"))
    )
    (net (code "110") (name "unconnected-(X2-PadB17)") (class "Default")
      (node (ref "X2") (pin "B17") (pinfunction "B17_B17") (pintype "passive"))
    )
    (net (code "111") (name "unconnected-(X2-PadB18)") (class "Default")
      (node (ref "X2") (pin "B18") (pinfunction "B18_B18") (pintype "passive"))
    )
    (net (code "112") (name "unconnected-(X2-PadB19)") (class "Default")
      (node (ref "X2") (pin "B19") (pinfunction "B19_B19") (pintype "passive"))
    )
    (net (code "113") (name "unconnected-(X2-PadB20)") (class "Default")
      (node (ref "X2") (pin "B20") (pinfunction "B20_B20") (pintype "passive"))
    )
    (net (code "114") (name "unconnected-(X2-PadB21)") (class "Default")
      (node (ref "X2") (pin "B21") (pinfunction "B21_B21") (pintype "passive"))
    )
    (net (code "115") (name "unconnected-(X2-PadB22)") (class "Default")
      (node (ref "X2") (pin "B22") (pinfunction "B22_B22") (pintype "passive"))
    )
    (net (code "116") (name "unconnected-(X2-PadB23)") (class "Default")
      (node (ref "X2") (pin "B23") (pinfunction "B23_B23") (pintype "passive"))
    )
    (net (code "117") (name "unconnected-(X2-PadB24)") (class "Default")
      (node (ref "X2") (pin "B24") (pinfunction "B24_B24") (pintype "passive"))
    )
    (net (code "118") (name "unconnected-(X2-PadB25)") (class "Default")
      (node (ref "X2") (pin "B25") (pinfunction "B25_B25") (pintype "passive"))
    )
  )
)
